# schematic.net
KiCad netlist of a schematic drawn in EAGLE
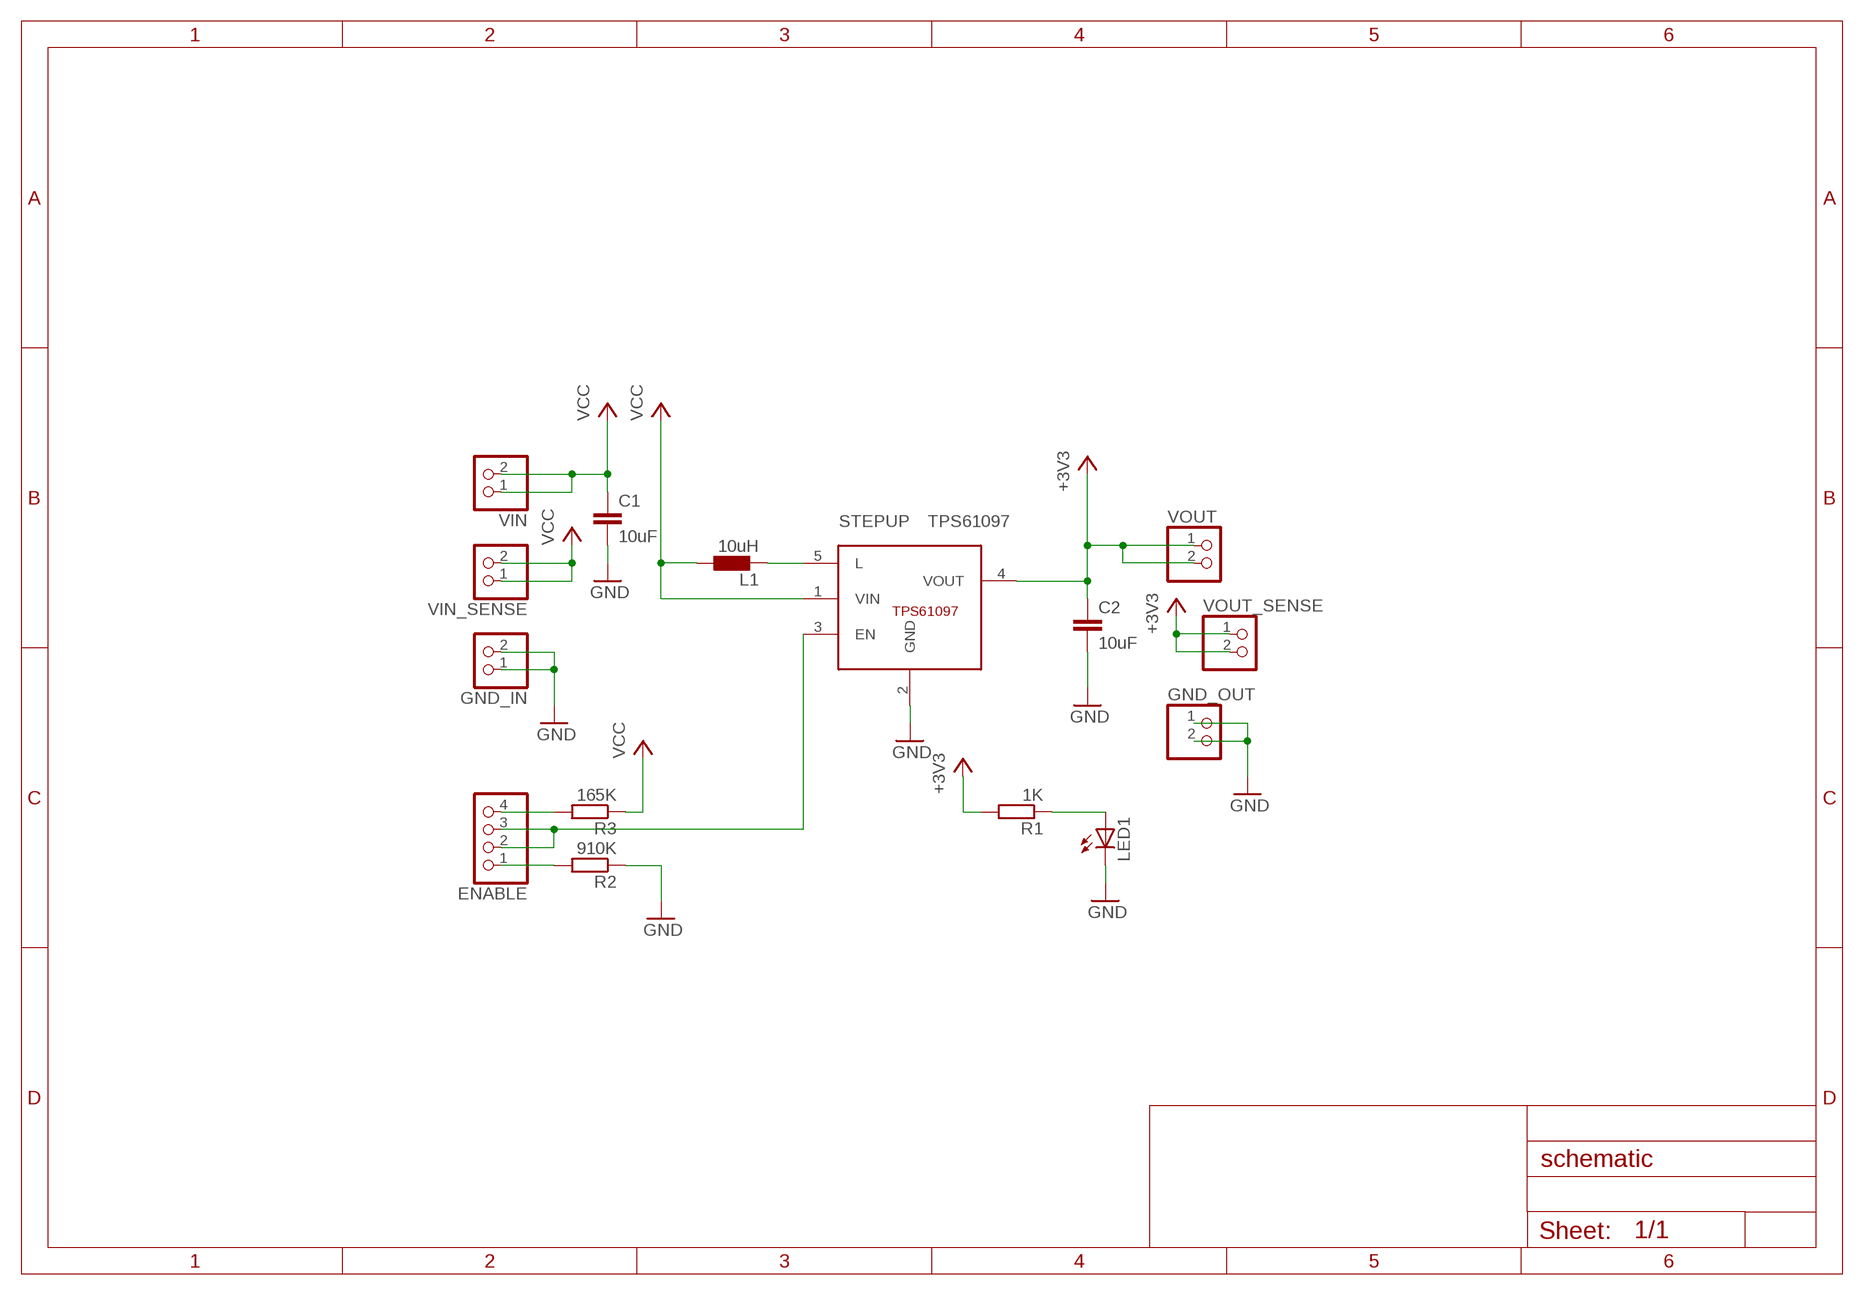
[diagram p0: schematic, sheet 1]

(export (version "E")
  (design (tool "Eeschema 10.0.6"))
  (components
    (comp (ref "C1")
      (value "10uF")
      (footprint "eagle-import:C1206")
      (libsource (lib "eagle-import") (part "C-EUC1206"))
    )
    (comp (ref "C2")
      (value "10uF")
      (footprint "eagle-import:C1206")
      (libsource (lib "eagle-import") (part "C-EUC1206"))
    )
    (comp (ref "ENABLE")
      (value "PINHD-1X4")
      (footprint "eagle-import:1X04")
      (libsource (lib "eagle-import") (part "PINHD-1X4"))
    )
    (comp (ref "GND_IN")
      (value "PINHD-1X2")
      (footprint "eagle-import:1X02")
      (libsource (lib "eagle-import") (part "PINHD-1X2"))
    )
    (comp (ref "GND_OUT")
      (value "PINHD-1X2")
      (footprint "eagle-import:1X02")
      (libsource (lib "eagle-import") (part "PINHD-1X2"))
    )
    (comp (ref "L1")
      (value "10uH")
      (footprint "eagle-import:L4532P")
      (libsource (lib "eagle-import") (part "LL4532P"))
    )
    (comp (ref "LED1")
      (value "LEDCHIP-LED0805")
      (footprint "eagle-import:CHIP-LED0805")
      (libsource (lib "eagle-import") (part "LEDCHIP-LED0805"))
    )
    (comp (ref "R1")
      (value "1K")
      (footprint "eagle-import:R0805")
      (libsource (lib "eagle-import") (part "R-EU_R0805"))
    )
    (comp (ref "R2")
      (value "910K")
      (footprint "eagle-import:R0805")
      (libsource (lib "eagle-import") (part "R-EU_R0805"))
    )
    (comp (ref "R3")
      (value "165K")
      (footprint "eagle-import:R0805")
      (libsource (lib "eagle-import") (part "R-EU_R0805"))
    )
    (comp (ref "STEPUP")
      (value "TPS61097")
      (footprint "eagle-import:SOT-23")
      (libsource (lib "eagle-import") (part "TPS61097"))
    )
    (comp (ref "VIN")
      (value "PINHD-1X2")
      (footprint "eagle-import:1X02")
      (libsource (lib "eagle-import") (part "PINHD-1X2"))
    )
    (comp (ref "VIN_SENSE")
      (value "PINHD-1X2")
      (footprint "eagle-import:1X02")
      (libsource (lib "eagle-import") (part "PINHD-1X2"))
    )
    (comp (ref "VOUT")
      (value "PINHD-1X2")
      (footprint "eagle-import:1X02")
      (libsource (lib "eagle-import") (part "PINHD-1X2"))
    )
    (comp (ref "VOUT_SENSE")
      (value "PINHD-1X2")
      (footprint "eagle-import:1X02")
      (libsource (lib "eagle-import") (part "PINHD-1X2"))
    )
  )
  (nets
    (net (code "1") (name "+3V3") (class "Default")
      (node (ref "C2") (pin "1") (pinfunction "1_1") (pintype "passive"))
      (node (ref "R1") (pin "2") (pinfunction "2_2") (pintype "passive"))
      (node (ref "STEPUP") (pin "4") (pinfunction "VOUT_4") (pintype "bidirectional"))
      (node (ref "VOUT") (pin "1") (pinfunction "1_1") (pintype "passive"))
      (node (ref "VOUT") (pin "2") (pinfunction "2_2") (pintype "passive"))
      (node (ref "VOUT_SENSE") (pin "1") (pinfunction "1_1") (pintype "passive"))
      (node (ref "VOUT_SENSE") (pin "2") (pinfunction "2_2") (pintype "passive"))
    )
    (net (code "2") (name "GND") (class "Default")
      (node (ref "C1") (pin "2") (pinfunction "2_2") (pintype "passive"))
      (node (ref "C2") (pin "2") (pinfunction "2_2") (pintype "passive"))
      (node (ref "GND_IN") (pin "1") (pinfunction "1_1") (pintype "passive"))
      (node (ref "GND_IN") (pin "2") (pinfunction "2_2") (pintype "passive"))
      (node (ref "GND_OUT") (pin "1") (pinfunction "1_1") (pintype "passive"))
      (node (ref "GND_OUT") (pin "2") (pinfunction "2_2") (pintype "passive"))
      (node (ref "LED1") (pin "C") (pinfunction "C_C") (pintype "passive"))
      (node (ref "R2") (pin "1") (pinfunction "1_1") (pintype "passive"))
      (node (ref "STEPUP") (pin "2") (pinfunction "GND_2") (pintype "bidirectional"))
    )
    (net (code "3") (name "Net-(ENABLE-Pad1)") (class "Default")
      (node (ref "ENABLE") (pin "1") (pinfunction "1_1") (pintype "passive"))
      (node (ref "R2") (pin "2") (pinfunction "2_2") (pintype "passive"))
    )
    (net (code "4") (name "Net-(ENABLE-Pad4)") (class "Default")
      (node (ref "ENABLE") (pin "4") (pinfunction "4_4") (pintype "passive"))
      (node (ref "R3") (pin "2") (pinfunction "2_2") (pintype "passive"))
    )
    (net (code "5") (name "Net-(LED1-PadA)") (class "Default")
      (node (ref "LED1") (pin "A") (pinfunction "A_A") (pintype "passive"))
      (node (ref "R1") (pin "1") (pinfunction "1_1") (pintype "passive"))
    )
    (net (code "6") (name "Net-(STEPUP-EN)") (class "Default")
      (node (ref "ENABLE") (pin "2") (pinfunction "2_2") (pintype "passive"))
      (node (ref "ENABLE") (pin "3") (pinfunction "3_3") (pintype "passive"))
      (node (ref "STEPUP") (pin "3") (pinfunction "EN_3") (pintype "bidirectional"))
    )
    (net (code "7") (name "Net-(STEPUP-L)") (class "Default")
      (node (ref "L1") (pin "2") (pinfunction "2_2") (pintype "passive"))
      (node (ref "STEPUP") (pin "5") (pinfunction "L_5") (pintype "bidirectional"))
    )
    (net (code "8") (name "VCC") (class "Default")
      (node (ref "C1") (pin "1") (pinfunction "1_1") (pintype "passive"))
      (node (ref "L1") (pin "1") (pinfunction "1_1") (pintype "passive"))
      (node (ref "R3") (pin "1") (pinfunction "1_1") (pintype "passive"))
      (node (ref "STEPUP") (pin "1") (pinfunction "VIN_1") (pintype "bidirectional"))
      (node (ref "VIN") (pin "1") (pinfunction "1_1") (pintype "passive"))
      (node (ref "VIN") (pin "2") (pinfunction "2_2") (pintype "passive"))
      (node (ref "VIN_SENSE") (pin "1") (pinfunction "1_1") (pintype "passive"))
      (node (ref "VIN_SENSE") (pin "2") (pinfunction "2_2") (pintype "passive"))
    )
  )
)
